# Peripherals_HUMA-mini.net
KiCad netlist of a schematic drawn in Altium Designer
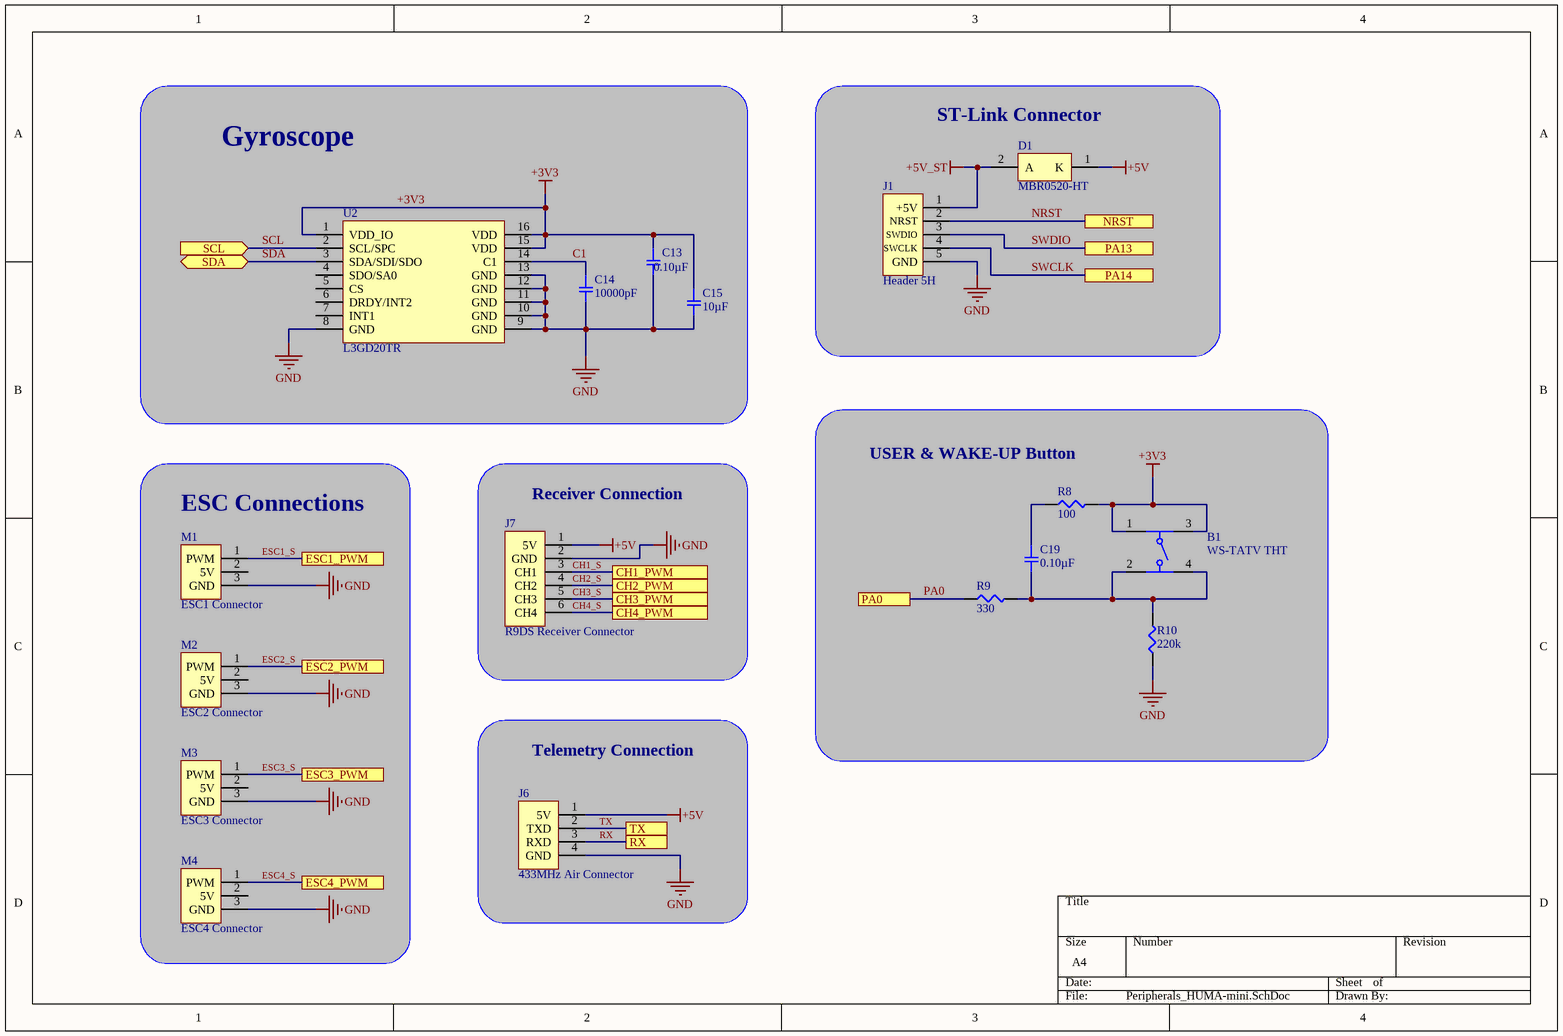
[diagram p0: Peripherals_HUMA-mini.SchDoc]

(export (version "E")
  (design (tool "Eeschema 10.0.6"))
  (components
    (comp (ref "B1")
      (value "WS-TATV THT")
      (footprint "4301x60507x6")
      (description "WS-TATV THT Tact Switch 6x6mm, height 5mm, 260gf")
      (fields (field (name "PART NUMBER") "430156050726") (field (name "PUBLISHER") "Wurth Elektronik"))
      (libsource (lib "430186050716_Altium_WS-TATV_rev19a") (part "430156050726"))
    )
    (comp (ref "C13")
      (value "0.10µF")
      (footprint "SMD-0805C")
      (description "CAP CER 0.1UF 25V X7R 0805")
      (fields
        (field (name "DIGI-KEY PART NUMBER") "490-12754-1-ND")
        (field (name "PART NUMBER") "GRM219R71E104KA01D")
      )
      (libsource (lib "Capacitors_Murata") (part "GRM219R71E104KA01D"))
    )
    (comp (ref "C14")
      (value "10000pF")
      (footprint "SMD-0805C")
      (description "CAP CER 10000PF 25V X7R 0805")
      (fields
        (field (name "DIGI-KEY PART NUMBER") "490-4424-1-ND")
        (field (name "PART NUMBER") "LLA215R71E103MA14L")
      )
      (libsource (lib "Capacitors_Murata") (part "LLA215R71E103MA14L"))
    )
    (comp (ref "C15")
      (value "10µF")
      (footprint "SMD-0805C")
      (description "CAP CER 10UF 16V X6S 0805")
      (fields
        (field (name "DIGI-KEY PART NUMBER") "490-5519-1-ND")
        (field (name "PART NUMBER") "GRM21BC81C106KA73L")
      )
      (libsource (lib "Capacitors_Murata") (part "GRM21BC81C106KA73L"))
    )
    (comp (ref "C19")
      (value "0.10µF")
      (footprint "SMD-0805C")
      (description "CAP CER 0.1UF 10V U2J 0805")
      (fields
        (field (name "DIGI-KEY PART NUMBER") "490-11592-1-ND")
        (field (name "PART NUMBER") "GRM21B7U1A104JA01L")
      )
      (libsource (lib "Capacitors_Murata") (part "GRM21B7U1A104JA01L"))
    )
    (comp (ref "D1")
      (value "MBR0520-HT")
      (footprint "ONSC-SOD-123-2-425-04_V")
      (description "20V 0.5A Schottky Power Rectifier, 2-Pin SOD-123, Tape and Reel")
      (fields (field (name "MANUFACTURER") "On Semiconductor") (field (name "PARTNUMBER") "MBR0520LT1"))
      (libsource (lib "ON Semi Schottky Diodes & Schottky Rectifiers") (part "MBR0520LT1"))
    )
    (comp (ref "J1")
      (value "Header 5H")
      (footprint "HDR1X5H")
      (description "Header, 5-Pin, Right Angle")
      (fields (field (name "PUBLISHER") "Altium Limited"))
      (libsource (lib "Miscellaneous Connectors") (part "Header 5H"))
    )
    (comp (ref "J6")
      (value "433MHz Air Connector")
      (footprint "HDR1X4H")
      (description "Header, 4-Pin, Right Angle")
      (fields (field (name "PUBLISHER") "Altium Limited"))
      (libsource (lib "Miscellaneous Connectors") (part "Header 4H"))
    )
    (comp (ref "J7")
      (value "R9DS Receiver Connector")
      (footprint "HDR1X6H")
      (description "Header, 6-Pin, Right Angle")
      (fields (field (name "PUBLISHER") "Altium Limited"))
      (libsource (lib "Miscellaneous Connectors") (part "Header 6H"))
    )
    (comp (ref "M1")
      (value "ESC1 Connector")
      (footprint "HDR1X3H")
      (description "Header, 3-Pin, Right Angle")
      (fields (field (name "PUBLISHER") "Altium Limited"))
      (libsource (lib "Miscellaneous Connectors") (part "Header 3H"))
    )
    (comp (ref "M2")
      (value "ESC2 Connector")
      (footprint "HDR1X3H")
      (description "Header, 3-Pin, Right Angle")
      (fields (field (name "PUBLISHER") "Altium Limited"))
      (libsource (lib "Miscellaneous Connectors") (part "Header 3H"))
    )
    (comp (ref "M3")
      (value "ESC3 Connector")
      (footprint "HDR1X3H")
      (description "Header, 3-Pin, Right Angle")
      (fields (field (name "PUBLISHER") "Altium Limited"))
      (libsource (lib "Miscellaneous Connectors") (part "Header 3H"))
    )
    (comp (ref "M4")
      (value "ESC4 Connector")
      (footprint "HDR1X3H")
      (description "Header, 3-Pin, Right Angle")
      (fields (field (name "PUBLISHER") "Altium Limited"))
      (libsource (lib "Miscellaneous Connectors") (part "Header 3H"))
    )
    (comp (ref "R8")
      (value "100")
      (footprint "SMD-0805-RES")
      (description "RES SMD 100 OHM 5% 1/2W 0805")
      (fields (field (name "PART NUMBER") "ERJ-P06J101V") (field (name "DIGI-KEY PART NUMBER") "P100ADCT-ND"))
      (libsource (lib "Resistors_Panasonic") (part "ERJ-P06J101V"))
    )
    (comp (ref "R9")
      (value "330")
      (footprint "SMD-0805-RES")
      (description "RES SMD 330 OHM 5% 1/2W 0805")
      (fields (field (name "PART NUMBER") "ERJ-P6WJ331V") (field (name "DIGI-KEY PART NUMBER") "P16948CT-ND"))
      (libsource (lib "Resistors_Panasonic") (part "ERJ-P6WJ331V"))
    )
    (comp (ref "R10")
      (value "220k")
      (footprint "SMD-0805-RES")
      (description "RES SMD 220K OHM 5% 1/2W 0805")
      (fields
        (field (name "PART NUMBER") "ERJ-P06J224V")
        (field (name "DIGI-KEY PART NUMBER") "P220KADCT-ND")
      )
      (libsource (lib "Resistors_Panasonic") (part "ERJ-P06J224V"))
    )
    (comp (ref "U2")
      (value "L3GD20TR")
      (footprint "LGA16C65P6X6_400X400X100")
      (description "Gyroscope X (Pitch), Y (Roll), Z (Yaw) ±250, 500, 2000 47.5Hz ~ 380Hz I²C, SPI 16-LGA (4x4)")
      (libsource (lib "L3GD20TR_MEMS") (part "L3GD20TR"))
    )
  )
  (nets
    (net (code "1") (name "+3V3") (class "Default")
      (node (ref "B1") (pin "1") (pinfunction "1_1") (pintype "passive"))
      (node (ref "B1") (pin "3") (pinfunction "3_3") (pintype "passive"))
      (node (ref "C13") (pin "1") (pinfunction "1_1") (pintype "passive"))
      (node (ref "C15") (pin "1") (pinfunction "1_1") (pintype "passive"))
      (node (ref "R8") (pin "2") (pinfunction "2_2") (pintype "passive"))
      (node (ref "U2") (pin "1") (pinfunction "VDD_IO_1") (pintype "passive"))
      (node (ref "U2") (pin "15") (pinfunction "VDD_15") (pintype "passive"))
      (node (ref "U2") (pin "16") (pinfunction "VDD_16") (pintype "passive"))
    )
    (net (code "2") (name "+5V") (class "Default")
      (node (ref "D1") (pin "1") (pinfunction "K_1") (pintype "passive"))
      (node (ref "J6") (pin "1") (pinfunction "5V_1") (pintype "passive"))
      (node (ref "J7") (pin "1") (pinfunction "5V_1") (pintype "passive"))
    )
    (net (code "3") (name "+5V_ST") (class "Default")
      (node (ref "D1") (pin "2") (pinfunction "A_2") (pintype "passive"))
      (node (ref "J1") (pin "1") (pinfunction "+5V_1") (pintype "passive"))
    )
    (net (code "4") (name "/C1") (class "Default")
      (node (ref "C14") (pin "1") (pinfunction "1_1") (pintype "passive"))
      (node (ref "U2") (pin "14") (pinfunction "C1_14") (pintype "passive"))
    )
    (net (code "5") (name "/CH1_S") (class "Default")
      (node (ref "J7") (pin "3") (pinfunction "CH1_3") (pintype "passive"))
    )
    (net (code "6") (name "/CH2_S") (class "Default")
      (node (ref "J7") (pin "4") (pinfunction "CH2_4") (pintype "passive"))
    )
    (net (code "7") (name "/CH3_S") (class "Default")
      (node (ref "J7") (pin "5") (pinfunction "CH3_5") (pintype "passive"))
    )
    (net (code "8") (name "/CH4_S") (class "Default")
      (node (ref "J7") (pin "6") (pinfunction "CH4_6") (pintype "passive"))
    )
    (net (code "9") (name "/ESC1_S") (class "Default")
      (node (ref "M1") (pin "1") (pinfunction "PWM_1") (pintype "passive"))
    )
    (net (code "10") (name "/ESC2_S") (class "Default")
      (node (ref "M2") (pin "1") (pinfunction "PWM_1") (pintype "passive"))
    )
    (net (code "11") (name "/ESC3_S") (class "Default")
      (node (ref "M3") (pin "1") (pinfunction "PWM_1") (pintype "passive"))
    )
    (net (code "12") (name "/ESC4_S") (class "Default")
      (node (ref "M4") (pin "1") (pinfunction "PWM_1") (pintype "passive"))
    )
    (net (code "13") (name "/NRST") (class "Default")
      (node (ref "J1") (pin "2") (pinfunction "NRST_2") (pintype "passive"))
    )
    (net (code "14") (name "/PA0") (class "Default")
      (node (ref "R9") (pin "1") (pinfunction "1_1") (pintype "passive"))
    )
    (net (code "15") (name "/RX") (class "Default")
      (node (ref "J6") (pin "3") (pinfunction "RXD_3") (pintype "passive"))
    )
    (net (code "16") (name "/SCL") (class "Default")
      (node (ref "U2") (pin "2") (pinfunction "SCL/SPC_2") (pintype "passive"))
    )
    (net (code "17") (name "/SDA") (class "Default")
      (node (ref "U2") (pin "3") (pinfunction "SDA/SDI/SDO_3") (pintype "passive"))
    )
    (net (code "18") (name "/SWCLK") (class "Default")
      (node (ref "J1") (pin "4") (pinfunction "SWCLK_4") (pintype "passive"))
    )
    (net (code "19") (name "/SWDIO") (class "Default")
      (node (ref "J1") (pin "3") (pinfunction "SWDIO_3") (pintype "passive"))
    )
    (net (code "20") (name "/TX") (class "Default")
      (node (ref "J6") (pin "2") (pinfunction "TXD_2") (pintype "passive"))
    )
    (net (code "21") (name "GND") (class "Default")
      (node (ref "C13") (pin "2") (pinfunction "2_2") (pintype "passive"))
      (node (ref "C14") (pin "2") (pinfunction "2_2") (pintype "passive"))
      (node (ref "C15") (pin "2") (pinfunction "2_2") (pintype "passive"))
      (node (ref "J1") (pin "5") (pinfunction "GND_5") (pintype "passive"))
      (node (ref "J6") (pin "4") (pinfunction "GND_4") (pintype "passive"))
      (node (ref "J7") (pin "2") (pinfunction "GND_2") (pintype "passive"))
      (node (ref "M1") (pin "3") (pinfunction "GND_3") (pintype "passive"))
      (node (ref "M2") (pin "3") (pinfunction "GND_3") (pintype "passive"))
      (node (ref "M3") (pin "3") (pinfunction "GND_3") (pintype "passive"))
      (node (ref "M4") (pin "3") (pinfunction "GND_3") (pintype "passive"))
      (node (ref "R10") (pin "1") (pinfunction "1_1") (pintype "passive"))
      (node (ref "U2") (pin "10") (pinfunction "GND_10") (pintype "passive"))
      (node (ref "U2") (pin "11") (pinfunction "GND_11") (pintype "passive"))
      (node (ref "U2") (pin "12") (pinfunction "GND_12") (pintype "passive"))
      (node (ref "U2") (pin "13") (pinfunction "GND_13") (pintype "passive"))
      (node (ref "U2") (pin "8") (pinfunction "GND_8") (pintype "passive"))
      (node (ref "U2") (pin "9") (pinfunction "GND_9") (pintype "passive"))
    )
    (net (code "22") (name "Net-(B1-Pad2)") (class "Default")
      (node (ref "B1") (pin "2") (pinfunction "2_2") (pintype "passive"))
      (node (ref "B1") (pin "4") (pinfunction "4_4") (pintype "passive"))
      (node (ref "C19") (pin "2") (pinfunction "2_2") (pintype "passive"))
      (node (ref "R10") (pin "2") (pinfunction "2_2") (pintype "passive"))
      (node (ref "R9") (pin "2") (pinfunction "2_2") (pintype "passive"))
    )
    (net (code "23") (name "Net-(C19-Pad1)") (class "Default")
      (node (ref "C19") (pin "1") (pinfunction "1_1") (pintype "passive"))
      (node (ref "R8") (pin "1") (pinfunction "1_1") (pintype "passive"))
    )
    (net (code "24") (name "unconnected-(M1-5V-Pad2)") (class "Default")
      (node (ref "M1") (pin "2") (pinfunction "5V_2") (pintype "passive"))
    )
    (net (code "25") (name "unconnected-(M2-5V-Pad2)") (class "Default")
      (node (ref "M2") (pin "2") (pinfunction "5V_2") (pintype "passive"))
    )
    (net (code "26") (name "unconnected-(M3-5V-Pad2)") (class "Default")
      (node (ref "M3") (pin "2") (pinfunction "5V_2") (pintype "passive"))
    )
    (net (code "27") (name "unconnected-(M4-5V-Pad2)") (class "Default")
      (node (ref "M4") (pin "2") (pinfunction "5V_2") (pintype "passive"))
    )
    (net (code "28") (name "unconnected-(U2-CS-Pad5)") (class "Default")
      (node (ref "U2") (pin "5") (pinfunction "CS_5") (pintype "passive"))
    )
    (net (code "29") (name "unconnected-(U2-DRDY{slash}INT2-Pad6)") (class "Default")
      (node (ref "U2") (pin "6") (pinfunction "DRDY/INT2_6") (pintype "passive"))
    )
    (net (code "30") (name "unconnected-(U2-INT1-Pad7)") (class "Default")
      (node (ref "U2") (pin "7") (pinfunction "INT1_7") (pintype "passive"))
    )
    (net (code "31") (name "unconnected-(U2-SDO{slash}SA0-Pad4)") (class "Default")
      (node (ref "U2") (pin "4") (pinfunction "SDO/SA0_4") (pintype "passive"))
    )
  )
)
